# Sheet1.net
KiCad netlist of a schematic drawn in Altium Designer
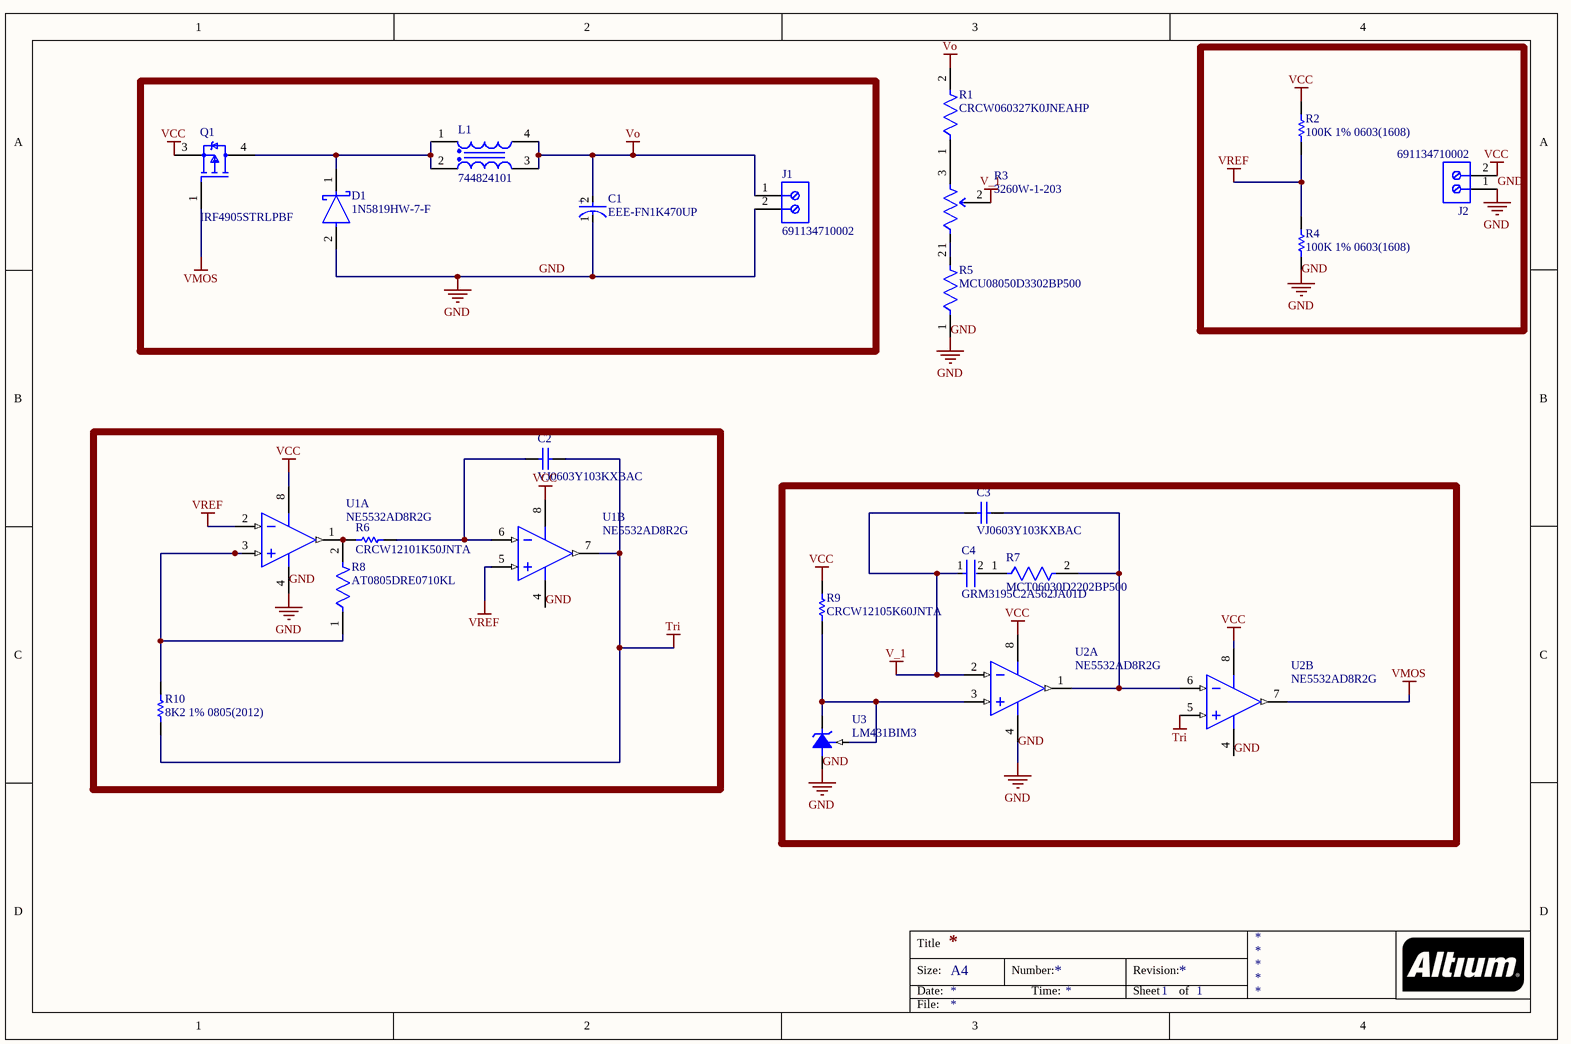
[diagram p0: Sheet1.SchDoc]

(export (version "E")
  (design (tool "Eeschema 10.0.6"))
  (components
    (comp (ref "C1")
      (value "EEE-FN1K470UP")
      (footprint "FP-FNF-MFG")
      (description "CAP ALUM 47UF 20% 80V SMD")
      (libsource (lib "Altium Content Vault") (part "203bc49f2ac43e59fd269a8c329ed05"))
    )
    (comp (ref "C2")
      (value "VJ0603Y103KXBAC")
      (footprint "CAPC1608X92X38NL15T08")
      (fields (field (name "MANUFACTURER") "Vitramon"))
      (libsource (lib "Altium Content Vault") (part "CAP"))
    )
    (comp (ref "C3")
      (value "VJ0603Y103KXBAC")
      (footprint "CAPC1608X92X38NL15T08")
      (fields (field (name "MANUFACTURER") "Vitramon"))
      (libsource (lib "Altium Content Vault") (part "CAP"))
    )
    (comp (ref "C4")
      (value "GRM3195C2A562JA01D")
      (footprint "FP-GRM319-0_15-IPC_A")
      (description "Chip Multilayer Ceramic Capacitors for General Purpose, 1206, 5600pF, C0G, 30ppm/°C, 5%, 100V")
      (fields (field (name "TOLERANCE") "5%"))
      (libsource (lib "Altium Content Vault") (part "b4654b650e69147ec39a6b967a45e02"))
    )
    (comp (ref "D1")
      (value "1N5819HW-7-F")
      (footprint "FP-SOD123-IPC_A")
      (description "DIODE SCHOTTKY 40V 1A SOD123")
      (libsource (lib "Altium Content Vault") (part "1d6ec82d83fb6aee721767c19dac4b9"))
    )
    (comp (ref "J1")
      (value "691134710002")
      (footprint "691134710002")
      (description "Wire-To-Board Terminal Block, 5mm Pitch, Horizontal, Screw, 2 Poles")
      (libsource (lib "Altium Content Vault") (part "TBL - 1R - 02P - Screw"))
    )
    (comp (ref "J2")
      (value "691134710002")
      (footprint "691134710002")
      (description "Wire-To-Board Terminal Block, 5mm Pitch, Horizontal, Screw, 2 Poles")
      (libsource (lib "Altium Content Vault") (part "TBL - 1R - 02P - Screw"))
    )
    (comp (ref "L1")
      (value "744824101")
      (footprint "WE-CMB_Type L_L27.5W18.5H33")
      (libsource (lib "Altium Content Vault") (part "WE-CMB"))
    )
    (comp (ref "Q1")
      (value "IRF4905STRLPBF")
      (footprint "FP-PG-TO263-3-MFG")
      (description "MOSFET P-CH 55V 42A D2PAK")
      (libsource (lib "Altium Content Vault") (part "a5278315d9cb221a74ee3a2ac99783a"))
    )
    (comp (ref "R1")
      (value "CRCW060327K0JNEAHP")
      (footprint "FP-CRCW0603-HPe3-IPC_B")
      (description "RES Thick Film, 27kΩ, 5%, 0.33W, 200ppm/°C, 0603")
      (fields (field (name "TOLERANCE") "5%"))
      (libsource (lib "Altium Content Vault") (part "1029c3af85768c4190bb7ad29bc67b5"))
    )
    (comp (ref "R2")
      (value "100K 1% 0603(1608)")
      (footprint "RESC0603(1608)_N")
      (description "100K 0.1W 1% 0603 (1608 Metric)  SMD")
      (fields (field (name "POWER") "0.1 W") (field (name "TOLERANCE") "1 %"))
      (libsource (lib "Altium Content Vault") (part "RES"))
    )
    (comp (ref "R3")
      (value "3260W-1-203")
      (footprint "FP-3260W-MFG")
      (description "3260W-1-203 Resistor Trimmer, Wirewound, 20 kOhm, ± 5%, 250 mW, 11 Turn, Multi Turn, Through Hole")
      (fields (field (name "TOLERANCE") "5%"))
      (libsource (lib "Altium Content Vault") (part "2dcfd2547301a7d3209a5e99acfd772"))
    )
    (comp (ref "R4")
      (value "100K 1% 0603(1608)")
      (footprint "RESC0603(1608)_N")
      (description "100K 0.1W 1% 0603 (1608 Metric)  SMD")
      (fields (field (name "POWER") "0.1 W") (field (name "TOLERANCE") "1 %"))
      (libsource (lib "Altium Content Vault") (part "RES"))
    )
    (comp (ref "R5")
      (value "MCU08050D3302BP500")
      (footprint "FP-MCU0805-IPC_A")
      (description "RES 1.05K OHM 0.5% 1/5W 0805")
      (fields (field (name "TOLERANCE") "0.1%"))
      (libsource (lib "Altium Content Vault") (part "1029c3af85768c4190bb7ad29bc67b5"))
    )
    (comp (ref "R6")
      (value "CRCW12101K50JNTA")
      (footprint "RESC3225X60X45NL20T20")
      (fields (field (name "MANUFACTURER") "Vishay Dale"))
      (libsource (lib "Altium Content Vault") (part "RES"))
    )
    (comp (ref "R7")
      (value "MCT06030D2202BP500")
      (footprint "FP-MCT0603-IPC_A")
      (description "RES SMD 100 OHM 1% 1/8W 0603")
      (fields (field (name "TOLERANCE") "0.1%"))
      (libsource (lib "Altium Content Vault") (part "1029c3af85768c4190bb7ad29bc67b5"))
    )
    (comp (ref "R8")
      (value "AT0805DRE0710KL")
      (footprint "FP-AT0805-MFG")
      (description "Thin Film Chip Resistors Automotive Grade 10kΩ 0.5% 50ppm/°C 0805")
      (fields (field (name "TOLERANCE") "0.5%"))
      (libsource (lib "Altium Content Vault") (part "1029c3af85768c4190bb7ad29bc67b5"))
    )
    (comp (ref "R9")
      (value "CRCW12105K60JNTA")
      (footprint "RESC3225X60X45LL20T20")
      (fields (field (name "MANUFACTURER") "Vishay Dale"))
      (libsource (lib "Altium Content Vault") (part "RES"))
    )
    (comp (ref "R10")
      (value "8K2 1% 0805(2012)")
      (footprint "RESC0805(2012)_N")
      (description "8K2 0.125W 1% 0805 (2012 Metric)  SMD")
      (fields (field (name "POWER") "0.125 W") (field (name "TOLERANCE") "1 %"))
      (libsource (lib "Altium Content Vault") (part "RES"))
    )
    (comp (ref "U1")
      (value "NE5532AD8R2G")
      (footprint "ONSC-SOIC-8-751-07_V")
      (fields (field (name "MANUFACTURER") "On Semiconductor"))
      (libsource (lib "Altium Content Vault") (part "ONSC-NE5532-SOIC-8-751-07"))
    )
    (comp (ref "U2")
      (value "NE5532AD8R2G")
      (footprint "ONSC-SOIC-8-751-07_V")
      (fields (field (name "MANUFACTURER") "On Semiconductor"))
      (libsource (lib "Altium Content Vault") (part "ONSC-NE5532-SOIC-8-751-07"))
    )
    (comp (ref "U3")
      (value "LM431BIM3")
      (footprint "DBZ0003A_M")
      (description "Adjustable Precision Zener Shunt Regulator, 3-pin SOT-23")
      (fields (field (name "MANUFACTURER") "Texas Instruments"))
      (libsource (lib "Altium Content Vault") (part "PM-REG-LM431M3-3"))
    )
  )
  (nets
    (net (code "1") (name "GND") (class "Default")
      (node (ref "C1") (pin "1") (pinfunction "C_1") (pintype "passive"))
      (node (ref "D1") (pin "2") (pinfunction "A_2") (pintype "passive"))
      (node (ref "J1") (pin "2") (pinfunction "2_2") (pintype "passive"))
      (node (ref "J2") (pin "1") (pinfunction "1_1") (pintype "passive"))
      (node (ref "R4") (pin "1") (pinfunction "1_1") (pintype "passive"))
      (node (ref "R5") (pin "1") (pinfunction "1_1") (pintype "passive"))
      (node (ref "U1") (pin "4") (pinfunction "V-_4") (pintype "power_in"))
      (node (ref "U2") (pin "4") (pinfunction "V-_4") (pintype "power_in"))
      (node (ref "U3") (pin "3") (pinfunction "A_3") (pintype "passive"))
    )
    (net (code "2") (name "Net-(C4-Pad2)") (class "Default")
      (node (ref "C4") (pin "2") (pinfunction "2_2") (pintype "passive"))
      (node (ref "R7") (pin "1") (pinfunction "1_1") (pintype "passive"))
    )
    (net (code "3") (name "Net-(D1-C)") (class "Default")
      (node (ref "D1") (pin "1") (pinfunction "C_1") (pintype "passive"))
      (node (ref "L1") (pin "1") (pinfunction "1_1") (pintype "passive"))
      (node (ref "L1") (pin "2") (pinfunction "2_2") (pintype "passive"))
      (node (ref "Q1") (pin "4") (pinfunction "D_4") (pintype "passive"))
    )
    (net (code "4") (name "Net-(R3-CCW)") (class "Default")
      (node (ref "R3") (pin "1") (pinfunction "CCW_1") (pintype "passive"))
      (node (ref "R5") (pin "2") (pinfunction "2_2") (pintype "passive"))
    )
    (net (code "5") (name "Net-(R3-CW)") (class "Default")
      (node (ref "R1") (pin "1") (pinfunction "1_1") (pintype "passive"))
      (node (ref "R3") (pin "3") (pinfunction "CW_3") (pintype "passive"))
    )
    (net (code "6") (name "Net-(U1A-INA+)") (class "Default")
      (node (ref "R10") (pin "2") (pinfunction "2_2") (pintype "passive"))
      (node (ref "R8") (pin "1") (pinfunction "1_1") (pintype "passive"))
      (node (ref "U1") (pin "3") (pinfunction "INA+_3") (pintype "input"))
    )
    (net (code "7") (name "Net-(U1A-OUTA)") (class "Default")
      (node (ref "R6") (pin "1") (pinfunction "1_1") (pintype "passive"))
      (node (ref "R8") (pin "2") (pinfunction "2_2") (pintype "passive"))
      (node (ref "U1") (pin "1") (pinfunction "OUTA_1") (pintype "output"))
    )
    (net (code "8") (name "Net-(U1B-INB-)") (class "Default")
      (node (ref "C2") (pin "1") (pinfunction "1_1") (pintype "passive"))
      (node (ref "R6") (pin "2") (pinfunction "2_2") (pintype "passive"))
      (node (ref "U1") (pin "6") (pinfunction "INB-_6") (pintype "input"))
    )
    (net (code "9") (name "Net-(U2A-INA+)") (class "Default")
      (node (ref "R9") (pin "1") (pinfunction "1_1") (pintype "passive"))
      (node (ref "U2") (pin "3") (pinfunction "INA+_3") (pintype "input"))
      (node (ref "U3") (pin "1") (pinfunction "K_1") (pintype "passive"))
      (node (ref "U3") (pin "2") (pinfunction "REF_2") (pintype "input"))
    )
    (net (code "10") (name "Net-(U2A-OUTA)") (class "Default")
      (node (ref "C3") (pin "2") (pinfunction "2_2") (pintype "passive"))
      (node (ref "R7") (pin "2") (pinfunction "2_2") (pintype "passive"))
      (node (ref "U2") (pin "1") (pinfunction "OUTA_1") (pintype "output"))
      (node (ref "U2") (pin "6") (pinfunction "INB-_6") (pintype "input"))
    )
    (net (code "11") (name "Tri") (class "Default")
      (node (ref "C2") (pin "2") (pinfunction "2_2") (pintype "passive"))
      (node (ref "R10") (pin "1") (pinfunction "1_1") (pintype "passive"))
      (node (ref "U1") (pin "7") (pinfunction "OUTB_7") (pintype "output"))
      (node (ref "U2") (pin "5") (pinfunction "INB+_5") (pintype "input"))
    )
    (net (code "12") (name "VCC") (class "Default")
      (node (ref "J2") (pin "2") (pinfunction "2_2") (pintype "passive"))
      (node (ref "Q1") (pin "3") (pinfunction "S_3") (pintype "passive"))
      (node (ref "R2") (pin "2") (pinfunction "2_2") (pintype "passive"))
      (node (ref "R9") (pin "2") (pinfunction "2_2") (pintype "passive"))
      (node (ref "U1") (pin "8") (pinfunction "V+_8") (pintype "power_in"))
      (node (ref "U2") (pin "8") (pinfunction "V+_8") (pintype "power_in"))
    )
    (net (code "13") (name "VMOS") (class "Default")
      (node (ref "Q1") (pin "1") (pinfunction "G_1") (pintype "passive"))
      (node (ref "U2") (pin "7") (pinfunction "OUTB_7") (pintype "output"))
    )
    (net (code "14") (name "VREF") (class "Default")
      (node (ref "R2") (pin "1") (pinfunction "1_1") (pintype "passive"))
      (node (ref "R4") (pin "2") (pinfunction "2_2") (pintype "passive"))
      (node (ref "U1") (pin "2") (pinfunction "INA-_2") (pintype "input"))
      (node (ref "U1") (pin "5") (pinfunction "INB+_5") (pintype "input"))
    )
    (net (code "15") (name "V_1") (class "Default")
      (node (ref "C3") (pin "1") (pinfunction "1_1") (pintype "passive"))
      (node (ref "C4") (pin "1") (pinfunction "1_1") (pintype "passive"))
      (node (ref "R3") (pin "2") (pinfunction "WIPER_2") (pintype "passive"))
      (node (ref "U2") (pin "2") (pinfunction "INA-_2") (pintype "input"))
    )
    (net (code "16") (name "Vo") (class "Default")
      (node (ref "C1") (pin "2") (pinfunction "A_2") (pintype "passive"))
      (node (ref "J1") (pin "1") (pinfunction "1_1") (pintype "passive"))
      (node (ref "L1") (pin "3") (pinfunction "3_3") (pintype "passive"))
      (node (ref "L1") (pin "4") (pinfunction "4_4") (pintype "passive"))
      (node (ref "R1") (pin "2") (pinfunction "2_2") (pintype "passive"))
    )
  )
)
